# Blinky_v2.net
KiCad netlist of a schematic drawn in EAGLE
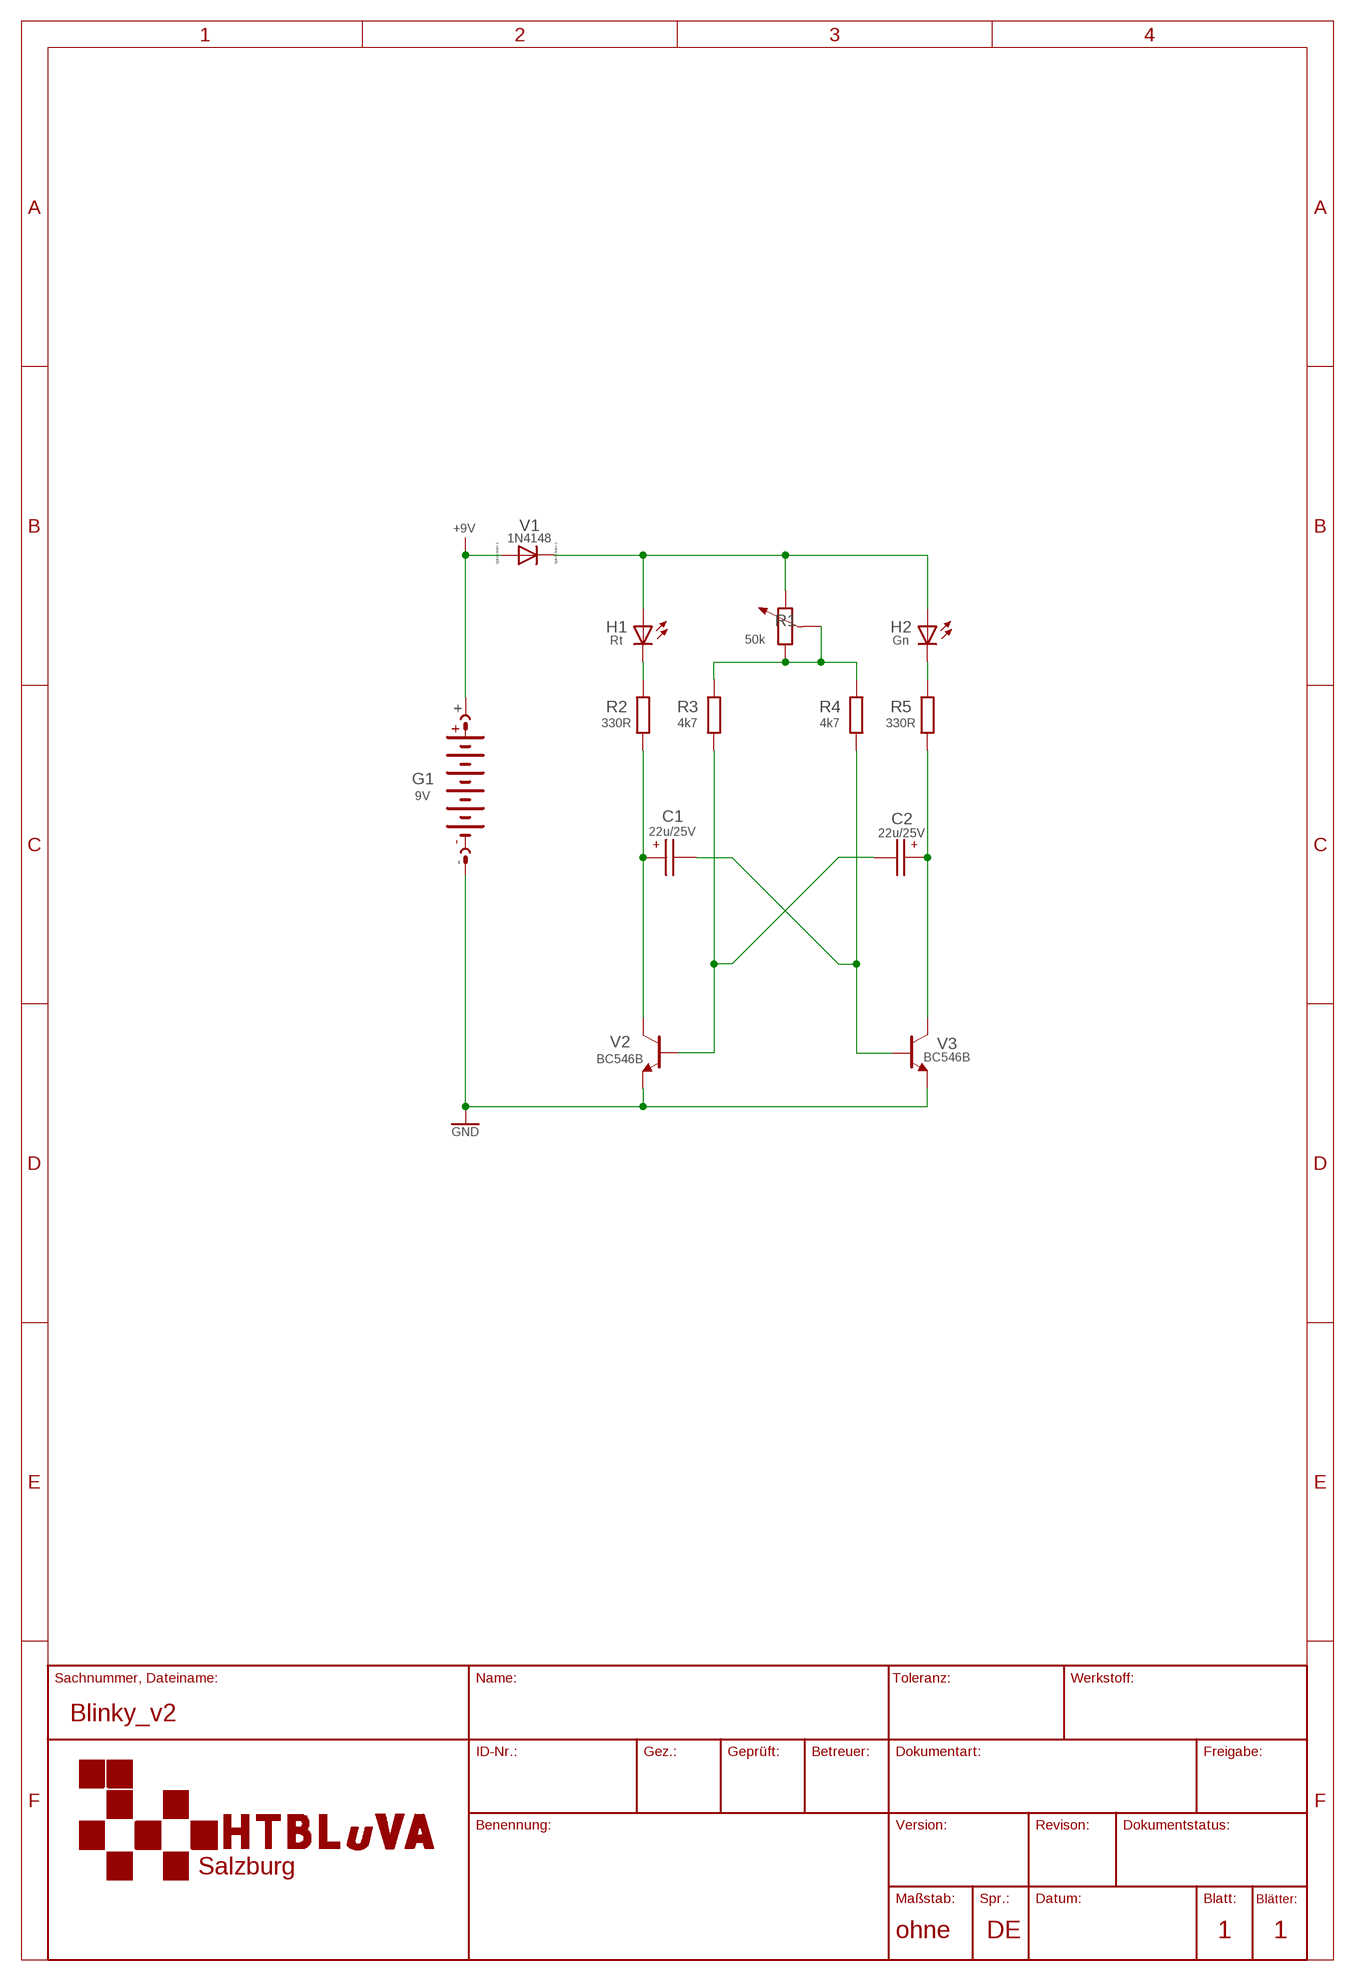
[diagram p0: schematic, sheet 1]

(export (version "E")
  (design (tool "Eeschema 10.0.6"))
  (components
    (comp (ref "C1")
      (value "22u/25V")
      (footprint "eagle-import:E2-5")
      (libsource (lib "eagle-import") (part "CPOL-V_E2-5"))
    )
    (comp (ref "C2")
      (value "22u/25V")
      (footprint "eagle-import:E2-5")
      (libsource (lib "eagle-import") (part "CPOL-V_E2-5"))
    )
    (comp (ref "G1")
      (value "9V")
      (footprint "eagle-import:AB9V")
      (libsource (lib "eagle-import") (part "AB9V9V"))
    )
    (comp (ref "H1")
      (value "Rt")
      (footprint "eagle-import:LED5MM")
      (libsource (lib "eagle-import") (part "LED_5MM"))
    )
    (comp (ref "H2")
      (value "Gn")
      (footprint "eagle-import:LED5MM")
      (libsource (lib "eagle-import") (part "LED_5MM"))
    )
    (comp (ref "R1")
      (value "50k")
      (footprint "eagle-import:PT-10")
      (libsource (lib "eagle-import") (part "R-POT_V_PT-10"))
    )
    (comp (ref "R2")
      (value "330R")
      (footprint "eagle-import:0207_10")
      (libsource (lib "eagle-import") (part "R-H_0207/10"))
    )
    (comp (ref "R3")
      (value "4k7")
      (footprint "eagle-import:0207_10")
      (libsource (lib "eagle-import") (part "R-H_0207/10"))
    )
    (comp (ref "R4")
      (value "4k7")
      (footprint "eagle-import:0207_10")
      (libsource (lib "eagle-import") (part "R-H_0207/10"))
    )
    (comp (ref "R5")
      (value "330R")
      (footprint "eagle-import:0207_10")
      (libsource (lib "eagle-import") (part "R-H_0207/10"))
    )
    (comp (ref "V1")
      (value "1N4148")
      (footprint "eagle-import:DO35-7")
      (libsource (lib "eagle-import") (part "1N4148_DO35-7"))
    )
    (comp (ref "V2")
      (value "BC546B")
      (footprint "eagle-import:TO92-EBC")
      (libsource (lib "eagle-import") (part "BC546B"))
    )
    (comp (ref "V3")
      (value "BC546B")
      (footprint "eagle-import:TO92-EBC")
      (libsource (lib "eagle-import") (part "BC546B"))
    )
  )
  (nets
    (net (code "1") (name "+9V") (class "Default")
      (node (ref "G1") (pin "+") (pinfunction "+_+") (pintype "passive"))
      (node (ref "V1") (pin "A") (pinfunction "A_A") (pintype "passive"))
    )
    (net (code "2") (name "GND") (class "Default")
      (node (ref "G1") (pin "-") (pinfunction "-_-") (pintype "passive"))
      (node (ref "V2") (pin "E") (pinfunction "E_E") (pintype "passive"))
      (node (ref "V3") (pin "E") (pinfunction "E_E") (pintype "passive"))
    )
    (net (code "3") (name "Net-(C1-Pad+)") (class "Default")
      (node (ref "C1") (pin "+") (pinfunction "+_+") (pintype "passive"))
      (node (ref "R2") (pin "1") (pinfunction "1_1") (pintype "passive"))
      (node (ref "V2") (pin "C") (pinfunction "C_C") (pintype "passive"))
    )
    (net (code "4") (name "Net-(C1-Pad-)") (class "Default")
      (node (ref "C1") (pin "-") (pinfunction "-_-") (pintype "passive"))
      (node (ref "R4") (pin "1") (pinfunction "1_1") (pintype "passive"))
      (node (ref "V3") (pin "B") (pinfunction "B_B") (pintype "passive"))
    )
    (net (code "5") (name "Net-(C2-Pad+)") (class "Default")
      (node (ref "C2") (pin "+") (pinfunction "+_+") (pintype "passive"))
      (node (ref "R5") (pin "1") (pinfunction "1_1") (pintype "passive"))
      (node (ref "V3") (pin "C") (pinfunction "C_C") (pintype "passive"))
    )
    (net (code "6") (name "Net-(C2-Pad-)") (class "Default")
      (node (ref "C2") (pin "-") (pinfunction "-_-") (pintype "passive"))
      (node (ref "R3") (pin "1") (pinfunction "1_1") (pintype "passive"))
      (node (ref "V2") (pin "B") (pinfunction "B_B") (pintype "passive"))
    )
    (net (code "7") (name "Net-(H1-C)") (class "Default")
      (node (ref "H1") (pin "K") (pinfunction "C_K") (pintype "passive"))
      (node (ref "R2") (pin "2") (pinfunction "2_2") (pintype "passive"))
    )
    (net (code "8") (name "Net-(H1-PadA)") (class "Default")
      (node (ref "H1") (pin "A") (pinfunction "A_A") (pintype "passive"))
      (node (ref "H2") (pin "A") (pinfunction "A_A") (pintype "passive"))
      (node (ref "R1") (pin "2") (pinfunction "2_2") (pintype "passive"))
      (node (ref "V1") (pin "C") (pinfunction "C_C") (pintype "passive"))
    )
    (net (code "9") (name "Net-(H2-C)") (class "Default")
      (node (ref "H2") (pin "K") (pinfunction "C_K") (pintype "passive"))
      (node (ref "R5") (pin "2") (pinfunction "2_2") (pintype "passive"))
    )
    (net (code "10") (name "Net-(R1-Pad1)") (class "Default")
      (node (ref "R1") (pin "1") (pinfunction "1_1") (pintype "passive"))
      (node (ref "R1") (pin "3") (pinfunction "3_3") (pintype "passive"))
      (node (ref "R3") (pin "2") (pinfunction "2_2") (pintype "passive"))
      (node (ref "R4") (pin "2") (pinfunction "2_2") (pintype "passive"))
    )
  )
)
